# sch-arduino-uno-r3-v1.net
KiCad netlist of a schematic drawn in Altium Designer
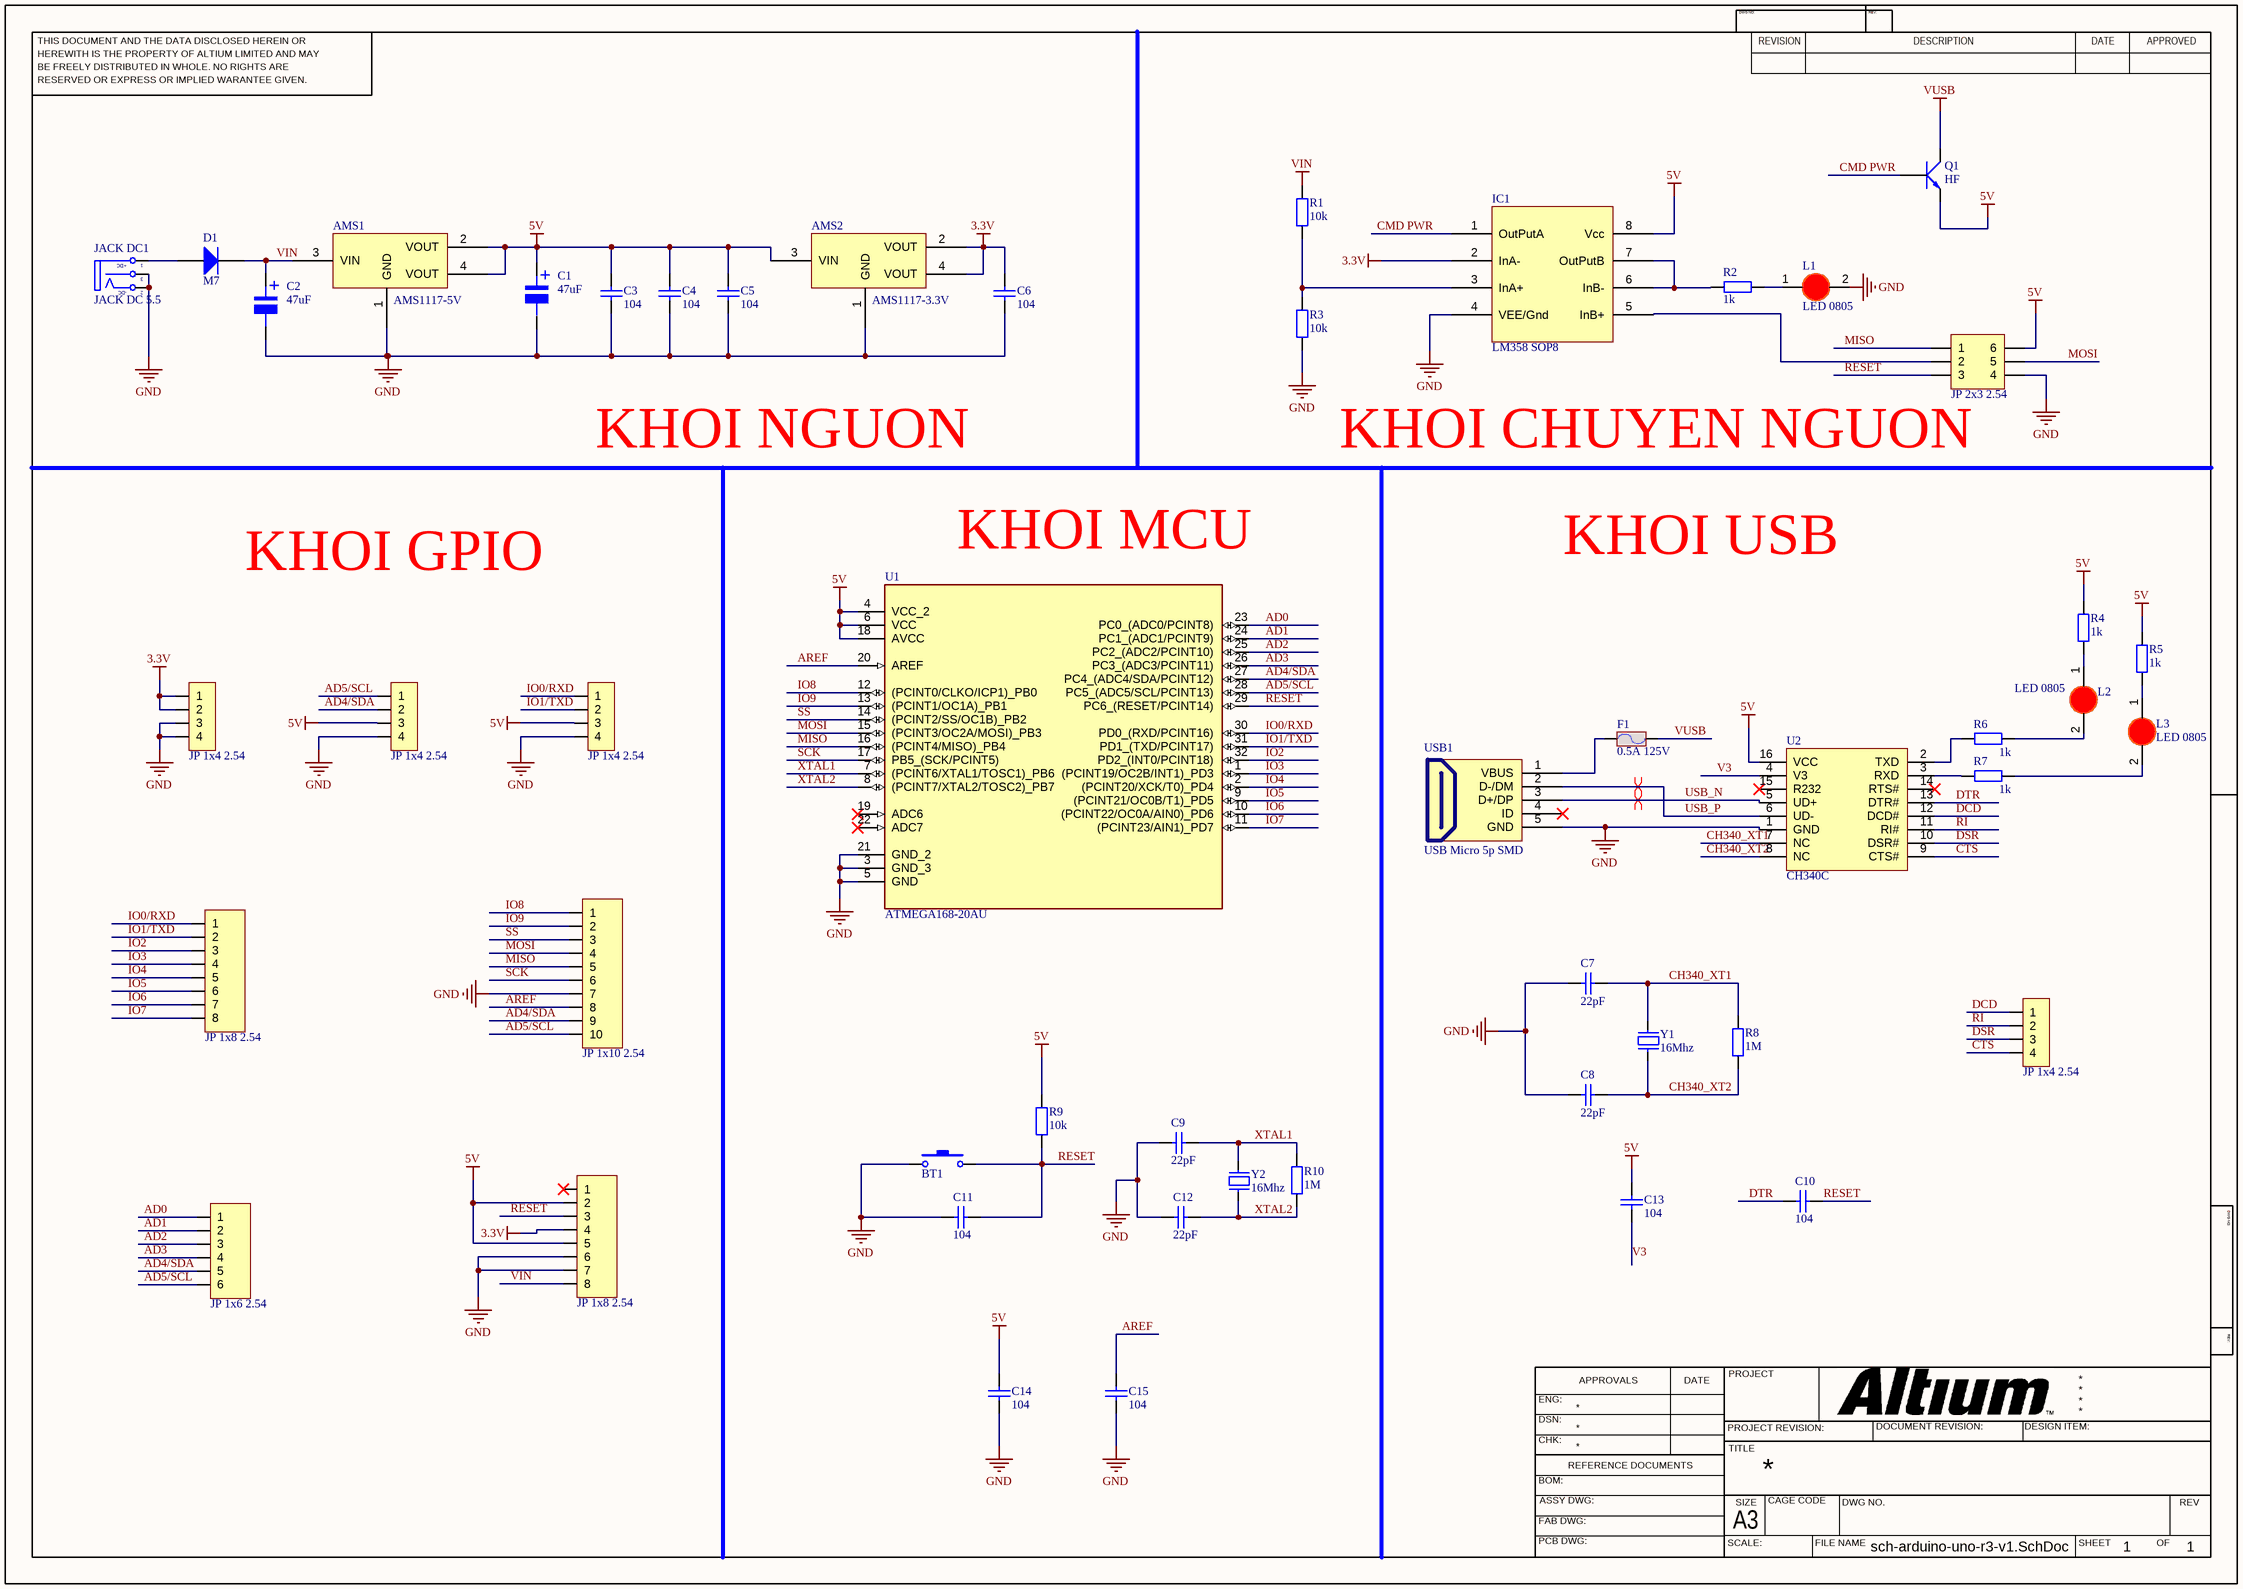
[diagram p0: sch-arduino-uno-r3-v1.SchDoc]

(export (version "E")
  (design (tool "Eeschema 10.0.6"))
  (components
    (comp (ref "AMS1")
      (value "AMS1117-5V")
      (footprint "SOT223")
      (description "Dán")
      (libsource (lib "Prj_ArduinoUno_Khanh") (part "AMS1117 SMD"))
    )
    (comp (ref "AMS2")
      (value "AMS1117-3.3V")
      (footprint "SOT223")
      (description "Dán")
      (libsource (lib "Prj_ArduinoUno_Khanh") (part "AMS1117 SMD_1"))
    )
    (comp (ref "BT1")
      (value "Nut Nhan 2 Chan SMD 3x6x2.5")
      (footprint "Nut Nhan 2 Chan SMD 3x6x2.5")
      (libsource (lib "Prj_ArduinoUno_Khanh") (part "Nut Nhan 2 Chan SMD 3x6x2.5"))
    )
    (comp (ref "C1")
      (value "47uF")
      (footprint "tu nhom 6.3 (d)")
      (description "Dán")
      (libsource (lib "Prj_ArduinoUno_Khanh") (part "Tu Nhom 47uF 50V"))
    )
    (comp (ref "C2")
      (value "47uF")
      (footprint "tu nhom 6.3 (d)")
      (description "Dán")
      (libsource (lib "Prj_ArduinoUno_Khanh") (part "Tu Nhom 47uF 50V"))
    )
    (comp (ref "C3")
      (value "104")
      (footprint "tu 0805")
      (description "Dán")
      (libsource (lib "Prj_ArduinoUno_Khanh") (part "Tu 0805 104 50V 10%"))
    )
    (comp (ref "C4")
      (value "104")
      (footprint "tu 0805")
      (description "Dán")
      (libsource (lib "Prj_ArduinoUno_Khanh") (part "Tu 0805 104 50V 10%"))
    )
    (comp (ref "C5")
      (value "104")
      (footprint "tu 0805")
      (description "Dán")
      (libsource (lib "Prj_ArduinoUno_Khanh") (part "Tu 0805 104 50V 10%"))
    )
    (comp (ref "C6")
      (value "104")
      (footprint "tu 0805")
      (description "Dán")
      (libsource (lib "Prj_ArduinoUno_Khanh") (part "Tu 0805 104 50V 10%"))
    )
    (comp (ref "C7")
      (value "22pF")
      (footprint "tu 0805")
      (description "Dán")
      (libsource (lib "Prj_ArduinoUno_Khanh") (part "Tu 0805 22pF 50V 10%"))
    )
    (comp (ref "C8")
      (value "22pF")
      (footprint "tu 0805")
      (description "Dán")
      (libsource (lib "Prj_ArduinoUno_Khanh") (part "Tu 0805 22pF 50V 10%"))
    )
    (comp (ref "C9")
      (value "22pF")
      (footprint "tu 0805")
      (description "Dán")
      (libsource (lib "Prj_ArduinoUno_Khanh") (part "Tu 0805 22pF 50V 10%"))
    )
    (comp (ref "C10")
      (value "104")
      (footprint "tu 0805")
      (description "Dán")
      (libsource (lib "Prj_ArduinoUno_Khanh") (part "Tu 0805 104 50V 10%"))
    )
    (comp (ref "C11")
      (value "104")
      (footprint "tu 0805")
      (description "Dán")
      (libsource (lib "Prj_ArduinoUno_Khanh") (part "Tu 0805 104 50V 10%"))
    )
    (comp (ref "C12")
      (value "22pF")
      (footprint "tu 0805")
      (description "Dán")
      (libsource (lib "Prj_ArduinoUno_Khanh") (part "Tu 0805 22pF 50V 10%"))
    )
    (comp (ref "C13")
      (value "104")
      (footprint "tu 0805")
      (description "Dán")
      (libsource (lib "Prj_ArduinoUno_Khanh") (part "Tu 0805 104 50V 10%"))
    )
    (comp (ref "C14")
      (value "104")
      (footprint "tu 0805")
      (description "Dán")
      (libsource (lib "Prj_ArduinoUno_Khanh") (part "Tu 0805 104 50V 10%"))
    )
    (comp (ref "C15")
      (value "104")
      (footprint "tu 0805")
      (description "Dán")
      (libsource (lib "Prj_ArduinoUno_Khanh") (part "Tu 0805 104 50V 10%"))
    )
    (comp (ref "D1")
      (value "M7")
      (footprint "DIODE SMA")
      (description "Dán")
      (libsource (lib "Prj_ArduinoUno_Khanh") (part "Diode M7 ( 4007 )"))
    )
    (comp (ref "F1")
      (value "0.5A 125V")
      (footprint "Cau Chi SMD1808")
      (description "Cau chi 0.5A 125V SMD1808")
      (libsource (lib "Prj_ArduinoUno_Khanh") (part "Cau chi 0.5A 125V SMD1808"))
    )
    (comp (ref "IC1")
      (value "LM358 SOP8")
      (footprint "SOP 8")
      (description "Dán")
      (libsource (lib "Prj_ArduinoUno_Khanh") (part "LM358 SOP8"))
    )
    (comp (ref "JACK DC1")
      (value "JACK DC 5.5")
      (footprint "JACK DC 5.5")
      (libsource (lib "Prj_ArduinoUno_Khanh") (part "JACK DC 5.5"))
    )
    (comp (ref "JP1")
      (value "JP 2x3 2.54")
      (footprint "JP 2x3 DT")
      (description "Cắm")
      (libsource (lib "Prj_ArduinoUno_Khanh") (part "JP 2x3 2.54 Duc Thang"))
    )
    (comp (ref "JP2")
      (value "JP 1x4 2.54")
      (footprint "JP 1x4 DT")
      (description "Cắm")
      (libsource (lib "Prj_ArduinoUno_Khanh") (part "JP 1x4 2.54 Duc Thang"))
    )
    (comp (ref "JP3")
      (value "JP 1x4 2.54")
      (footprint "JP 1x4 DT")
      (description "Cắm")
      (libsource (lib "Prj_ArduinoUno_Khanh") (part "JP 1x4 2.54 Duc Thang"))
    )
    (comp (ref "JP4")
      (value "JP 1x4 2.54")
      (footprint "JP 1x4 DT")
      (description "Cắm")
      (libsource (lib "Prj_ArduinoUno_Khanh") (part "JP 1x4 2.54 Duc Thang"))
    )
    (comp (ref "JP5")
      (value "JP 1x10 2.54")
      (footprint "JP 1x10 CT")
      (description "Cắm")
      (libsource (lib "Prj_ArduinoUno_Khanh") (part "JP 1x10 2.54 Cai Thang"))
    )
    (comp (ref "JP6")
      (value "JP 1x8 2.54")
      (footprint "JP 1x8 CT")
      (description "Cắm")
      (libsource (lib "Prj_ArduinoUno_Khanh") (part "JP 1x8 2.54 Cai Thang"))
    )
    (comp (ref "JP7")
      (value "JP 1x4 2.54")
      (footprint "JP 1x4 DT")
      (description "Cắm")
      (libsource (lib "Prj_ArduinoUno_Khanh") (part "JP 1x4 2.54 Duc Thang"))
    )
    (comp (ref "JP8")
      (value "JP 1x8 2.54")
      (footprint "JP 1x8 CT")
      (description "Cắm")
      (libsource (lib "Prj_ArduinoUno_Khanh") (part "JP 1x8 2.54 Cai Thang"))
    )
    (comp (ref "JP9")
      (value "JP 1x6 2.54")
      (footprint "JP 1x6 CT")
      (description "Cắm")
      (libsource (lib "Prj_ArduinoUno_Khanh") (part "JP 1x6 2.54 Cai Thang"))
    )
    (comp (ref "L1")
      (value "LED 0805")
      (footprint "LED-0805-Red")
      (description "Dán")
      (libsource (lib "Prj_ArduinoUno_Khanh") (part "LED 0805 Do"))
    )
    (comp (ref "L2")
      (value "LED 0805")
      (footprint "LED-0805-Red")
      (description "Dán")
      (libsource (lib "Prj_ArduinoUno_Khanh") (part "LED 0805 Do"))
    )
    (comp (ref "L3")
      (value "LED 0805")
      (footprint "LED-0805-Red")
      (description "Dán")
      (libsource (lib "Prj_ArduinoUno_Khanh") (part "LED 0805 Do"))
    )
    (comp (ref "Q1")
      (value "HF")
      (footprint "SOT23")
      (description "NPN transistor")
      (libsource (lib "Prj_ArduinoUno_Khanh") (part "C1815 HF SMD"))
    )
    (comp (ref "R1")
      (value "10k")
      (footprint "tro smd 0805")
      (description "Dán")
      (libsource (lib "Prj_ArduinoUno_Khanh") (part "Tro 0805 5% 10k"))
    )
    (comp (ref "R2")
      (value "1k")
      (footprint "tro smd 0805")
      (description "Dán")
      (libsource (lib "Prj_ArduinoUno_Khanh") (part "Tro 0805 1% 1k"))
    )
    (comp (ref "R3")
      (value "10k")
      (footprint "tro smd 0805")
      (description "Dán")
      (libsource (lib "Prj_ArduinoUno_Khanh") (part "Tro 0805 5% 10k"))
    )
    (comp (ref "R4")
      (value "1k")
      (footprint "tro smd 0805")
      (description "Dán")
      (libsource (lib "Prj_ArduinoUno_Khanh") (part "Tro 0805 1% 1k"))
    )
    (comp (ref "R5")
      (value "1k")
      (footprint "tro smd 0805")
      (description "Dán")
      (libsource (lib "Prj_ArduinoUno_Khanh") (part "Tro 0805 1% 1k"))
    )
    (comp (ref "R6")
      (value "1k")
      (footprint "tro smd 0805")
      (description "Dán")
      (libsource (lib "Prj_ArduinoUno_Khanh") (part "Tro 0805 1% 1k"))
    )
    (comp (ref "R7")
      (value "1k")
      (footprint "tro smd 0805")
      (description "Dán")
      (libsource (lib "Prj_ArduinoUno_Khanh") (part "Tro 0805 1% 1k"))
    )
    (comp (ref "R8")
      (value "1M")
      (footprint "tro smd 0805")
      (description "Dán")
      (libsource (lib "Prj_ArduinoUno_Khanh") (part "Tro 0805 5% 1M"))
    )
    (comp (ref "R9")
      (value "10k")
      (footprint "tro smd 0805")
      (description "Dán")
      (libsource (lib "Prj_ArduinoUno_Khanh") (part "Tro 0805 5% 10k"))
    )
    (comp (ref "R10")
      (value "1M")
      (footprint "tro smd 0805")
      (description "Dán")
      (libsource (lib "Prj_ArduinoUno_Khanh") (part "Tro 0805 5% 1M"))
    )
    (comp (ref "U1")
      (value "ATMEGA168-20AU")
      (footprint "ATMEGA168")
      (description "AVR AVRÂ® ATmega Microcontroller IC 8-Bit 20MHz 16KB _8K x 16_ FLASH 32-TQFP _7x7_")
      (fields (field (name "MF") "Microchip"))
      (libsource (lib "Prj_ArduinoUno_Khanh") (part "ATMEGA168-20AU"))
    )
    (comp (ref "U2")
      (value "CH340C")
      (footprint "SOIC16_50_284_25X90_SMT")
      (description "USB Bridge, USB to UART USB 2.0 UART Interface")
      (fields (field (name "MANUFACTURER") "Olimex"))
      (libsource (lib "Prj_ArduinoUno_Khanh") (part "IC_CH340C"))
    )
    (comp (ref "USB1")
      (value "USB Micro 5p SMD")
      (footprint "USB Micro 5p SMD")
      (description "USB Type B")
      (libsource (lib "Prj_ArduinoUno_Khanh") (part "USB Micro 5p SMD"))
    )
    (comp (ref "Y1")
      (value "16Mhz")
      (footprint "Thach Anh 2 chan SMD")
      (description "Crystal For all Crystal 2pin.")
      (libsource (lib "Prj_ArduinoUno_Khanh") (part "Thach Anh 2 chan SMD"))
    )
    (comp (ref "Y2")
      (value "16Mhz")
      (footprint "Thach Anh 2 chan SMD")
      (description "Crystal For all Crystal 2pin.")
      (libsource (lib "Prj_ArduinoUno_Khanh") (part "Thach Anh 2 chan SMD"))
    )
  )
  (nets
    (net (code "1") (name "/AD0") (class "Default")
      (node (ref "JP9") (pin "1") (pinfunction "1_1") (pintype "passive"))
      (node (ref "U1") (pin "23") (pinfunction "PC0_(ADC0/PCINT8)_23") (pintype "bidirectional"))
    )
    (net (code "2") (name "/AD1") (class "Default")
      (node (ref "JP9") (pin "2") (pinfunction "2_2") (pintype "passive"))
      (node (ref "U1") (pin "24") (pinfunction "PC1_(ADC1/PCINT9)_24") (pintype "bidirectional"))
    )
    (net (code "3") (name "/AD2") (class "Default")
      (node (ref "JP9") (pin "3") (pinfunction "3_3") (pintype "passive"))
      (node (ref "U1") (pin "25") (pinfunction "PC2_(ADC2/PCINT10)_25") (pintype "bidirectional"))
    )
    (net (code "4") (name "/AD3") (class "Default")
      (node (ref "JP9") (pin "4") (pinfunction "4_4") (pintype "passive"))
      (node (ref "U1") (pin "26") (pinfunction "PC3_(ADC3/PCINT11)_26") (pintype "bidirectional"))
    )
    (net (code "5") (name "/AD4{slash}SDA") (class "Default")
      (node (ref "JP3") (pin "2") (pinfunction "2_2") (pintype "passive"))
      (node (ref "JP5") (pin "9") (pinfunction "9_9") (pintype "passive"))
      (node (ref "JP9") (pin "5") (pinfunction "5_5") (pintype "passive"))
      (node (ref "U1") (pin "27") (pinfunction "PC4_(ADC4/SDA/PCINT12)_27") (pintype "bidirectional"))
    )
    (net (code "6") (name "/AD5{slash}SCL") (class "Default")
      (node (ref "JP3") (pin "1") (pinfunction "1_1") (pintype "passive"))
      (node (ref "JP5") (pin "10") (pinfunction "10_10") (pintype "passive"))
      (node (ref "JP9") (pin "6") (pinfunction "6_6") (pintype "passive"))
      (node (ref "U1") (pin "28") (pinfunction "PC5_(ADC5/SCL/PCINT13)_28") (pintype "bidirectional"))
    )
    (net (code "7") (name "/AREF") (class "Default")
      (node (ref "C15") (pin "1") (pinfunction "1_1") (pintype "passive"))
      (node (ref "JP5") (pin "8") (pinfunction "8_8") (pintype "passive"))
      (node (ref "U1") (pin "20") (pinfunction "AREF_20") (pintype "input"))
    )
    (net (code "8") (name "/CH340_XT1") (class "Default")
      (node (ref "C7") (pin "1") (pinfunction "1_1") (pintype "passive"))
      (node (ref "R8") (pin "2") (pinfunction "2_2") (pintype "passive"))
      (node (ref "U2") (pin "7") (pinfunction "NC_7") (pintype "passive"))
      (node (ref "Y1") (pin "2") (pinfunction "2_2") (pintype "passive"))
    )
    (net (code "9") (name "/CH340_XT2") (class "Default")
      (node (ref "C8") (pin "1") (pinfunction "1_1") (pintype "passive"))
      (node (ref "R8") (pin "1") (pinfunction "1_1") (pintype "passive"))
      (node (ref "U2") (pin "8") (pinfunction "NC_8") (pintype "passive"))
      (node (ref "Y1") (pin "1") (pinfunction "1_1") (pintype "passive"))
    )
    (net (code "10") (name "/CMD PWR") (class "Default")
      (node (ref "IC1") (pin "1") (pinfunction "OutPutA_1") (pintype "passive"))
      (node (ref "Q1") (pin "1") (pinfunction "B_1") (pintype "passive"))
    )
    (net (code "11") (name "/CTS") (class "Default")
      (node (ref "JP7") (pin "4") (pinfunction "4_4") (pintype "passive"))
      (node (ref "U2") (pin "9") (pinfunction "CTS#_9") (pintype "passive"))
    )
    (net (code "12") (name "/DCD") (class "Default")
      (node (ref "JP7") (pin "1") (pinfunction "1_1") (pintype "passive"))
      (node (ref "U2") (pin "12") (pinfunction "DCD#_12") (pintype "passive"))
    )
    (net (code "13") (name "/DSR") (class "Default")
      (node (ref "JP7") (pin "3") (pinfunction "3_3") (pintype "passive"))
      (node (ref "U2") (pin "10") (pinfunction "DSR#_10") (pintype "passive"))
    )
    (net (code "14") (name "/DTR") (class "Default")
      (node (ref "C10") (pin "1") (pinfunction "1_1") (pintype "passive"))
      (node (ref "U2") (pin "13") (pinfunction "DTR#_13") (pintype "passive"))
    )
    (net (code "15") (name "/IO0{slash}RXD") (class "Default")
      (node (ref "JP4") (pin "1") (pinfunction "1_1") (pintype "passive"))
      (node (ref "JP6") (pin "1") (pinfunction "1_1") (pintype "passive"))
      (node (ref "U1") (pin "30") (pinfunction "PD0_(RXD/PCINT16)_30") (pintype "bidirectional"))
    )
    (net (code "16") (name "/IO1{slash}TXD") (class "Default")
      (node (ref "JP4") (pin "2") (pinfunction "2_2") (pintype "passive"))
      (node (ref "JP6") (pin "2") (pinfunction "2_2") (pintype "passive"))
      (node (ref "U1") (pin "31") (pinfunction "PD1_(TXD/PCINT17)_31") (pintype "bidirectional"))
    )
    (net (code "17") (name "/IO2") (class "Default")
      (node (ref "JP6") (pin "3") (pinfunction "3_3") (pintype "passive"))
      (node (ref "U1") (pin "32") (pinfunction "PD2_(INT0/PCINT18)_32") (pintype "bidirectional"))
    )
    (net (code "18") (name "/IO3") (class "Default")
      (node (ref "JP6") (pin "4") (pinfunction "4_4") (pintype "passive"))
      (node (ref "U1") (pin "1") (pinfunction "(PCINT19/OC2B/INT1)_PD3_1") (pintype "bidirectional"))
    )
    (net (code "19") (name "/IO4") (class "Default")
      (node (ref "JP6") (pin "5") (pinfunction "5_5") (pintype "passive"))
      (node (ref "U1") (pin "2") (pinfunction "(PCINT20/XCK/T0)_PD4_2") (pintype "bidirectional"))
    )
    (net (code "20") (name "/IO5") (class "Default")
      (node (ref "JP6") (pin "6") (pinfunction "6_6") (pintype "passive"))
      (node (ref "U1") (pin "9") (pinfunction "(PCINT21/OC0B/T1)_PD5_9") (pintype "bidirectional"))
    )
    (net (code "21") (name "/IO6") (class "Default")
      (node (ref "JP6") (pin "7") (pinfunction "7_7") (pintype "passive"))
      (node (ref "U1") (pin "10") (pinfunction "(PCINT22/OC0A/AIN0)_PD6_10") (pintype "bidirectional"))
    )
    (net (code "22") (name "/IO7") (class "Default")
      (node (ref "JP6") (pin "8") (pinfunction "8_8") (pintype "passive"))
      (node (ref "U1") (pin "11") (pinfunction "(PCINT23/AIN1)_PD7_11") (pintype "bidirectional"))
    )
    (net (code "23") (name "/IO8") (class "Default")
      (node (ref "JP5") (pin "1") (pinfunction "1_1") (pintype "passive"))
      (node (ref "U1") (pin "12") (pinfunction "(PCINT0/CLKO/ICP1)_PB0_12") (pintype "bidirectional"))
    )
    (net (code "24") (name "/IO9") (class "Default")
      (node (ref "JP5") (pin "2") (pinfunction "2_2") (pintype "passive"))
      (node (ref "U1") (pin "13") (pinfunction "(PCINT1/OC1A)_PB1_13") (pintype "bidirectional"))
    )
    (net (code "25") (name "/MISO") (class "Default")
      (node (ref "JP1") (pin "1") (pinfunction "1_1") (pintype "passive"))
      (node (ref "JP5") (pin "5") (pinfunction "5_5") (pintype "passive"))
      (node (ref "U1") (pin "16") (pinfunction "(PCINT4/MISO)_PB4_16") (pintype "bidirectional"))
    )
    (net (code "26") (name "/MOSI") (class "Default")
      (node (ref "JP1") (pin "5") (pinfunction "5_5") (pintype "passive"))
      (node (ref "JP5") (pin "4") (pinfunction "4_4") (pintype "passive"))
      (node (ref "U1") (pin "15") (pinfunction "(PCINT3/OC2A/MOSI)_PB3_15") (pintype "bidirectional"))
    )
    (net (code "27") (name "/RESET") (class "Default")
      (node (ref "BT1") (pin "2") (pinfunction "2_2") (pintype "passive"))
      (node (ref "C10") (pin "2") (pinfunction "2_2") (pintype "passive"))
      (node (ref "C11") (pin "1") (pinfunction "1_1") (pintype "passive"))
      (node (ref "JP1") (pin "3") (pinfunction "3_3") (pintype "passive"))
      (node (ref "JP8") (pin "3") (pinfunction "3_3") (pintype "passive"))
      (node (ref "R9") (pin "1") (pinfunction "1_1") (pintype "passive"))
      (node (ref "U1") (pin "29") (pinfunction "PC6_(RESET/PCINT14)_29") (pintype "bidirectional"))
    )
    (net (code "28") (name "/RI") (class "Default")
      (node (ref "JP7") (pin "2") (pinfunction "2_2") (pintype "passive"))
      (node (ref "U2") (pin "11") (pinfunction "RI#_11") (pintype "passive"))
    )
    (net (code "29") (name "/SCK") (class "Default")
      (node (ref "JP5") (pin "6") (pinfunction "6_6") (pintype "passive"))
      (node (ref "U1") (pin "17") (pinfunction "PB5_(SCK/PCINT5)_17") (pintype "bidirectional"))
    )
    (net (code "30") (name "/SS") (class "Default")
      (node (ref "JP5") (pin "3") (pinfunction "3_3") (pintype "passive"))
      (node (ref "U1") (pin "14") (pinfunction "(PCINT2/SS/OC1B)_PB2_14") (pintype "bidirectional"))
    )
    (net (code "31") (name "/USB_N") (class "Default")
      (node (ref "U2") (pin "5") (pinfunction "UD+_5") (pintype "passive"))
      (node (ref "USB1") (pin "3") (pinfunction "D+/DP_3") (pintype "passive"))
    )
    (net (code "32") (name "/USB_P") (class "Default")
      (node (ref "U2") (pin "6") (pinfunction "UD-_6") (pintype "passive"))
      (node (ref "USB1") (pin "2") (pinfunction "D-/DM_2") (pintype "passive"))
    )
    (net (code "33") (name "/V3") (class "Default")
      (node (ref "C13") (pin "2") (pinfunction "2_2") (pintype "passive"))
      (node (ref "U2") (pin "4") (pinfunction "V3_4") (pintype "passive"))
    )
    (net (code "34") (name "/XTAL1") (class "Default")
      (node (ref "C9") (pin "1") (pinfunction "1_1") (pintype "passive"))
      (node (ref "R10") (pin "2") (pinfunction "2_2") (pintype "passive"))
      (node (ref "U1") (pin "7") (pinfunction "(PCINT6/XTAL1/TOSC1)_PB6_7") (pintype "bidirectional"))
      (node (ref "Y2") (pin "2") (pinfunction "2_2") (pintype "passive"))
    )
    (net (code "35") (name "/XTAL2") (class "Default")
      (node (ref "C12") (pin "1") (pinfunction "1_1") (pintype "passive"))
      (node (ref "R10") (pin "1") (pinfunction "1_1") (pintype "passive"))
      (node (ref "U1") (pin "8") (pinfunction "(PCINT7/XTAL2/TOSC2)_PB7_8") (pintype "bidirectional"))
      (node (ref "Y2") (pin "1") (pinfunction "1_1") (pintype "passive"))
    )
    (net (code "36") (name "3.3V") (class "Default")
      (node (ref "AMS2") (pin "2") (pinfunction "VOUT_2") (pintype "passive"))
      (node (ref "AMS2") (pin "4") (pinfunction "VOUT_4") (pintype "passive"))
      (node (ref "C6") (pin "1") (pinfunction "1_1") (pintype "passive"))
      (node (ref "IC1") (pin "2") (pinfunction "InA-_2") (pintype "passive"))
      (node (ref "JP2") (pin "1") (pinfunction "1_1") (pintype "passive"))
      (node (ref "JP2") (pin "2") (pinfunction "2_2") (pintype "passive"))
      (node (ref "JP8") (pin "4") (pinfunction "4_4") (pintype "passive"))
    )
    (net (code "37") (name "5V") (class "Default")
      (node (ref "AMS1") (pin "2") (pinfunction "VOUT_2") (pintype "passive"))
      (node (ref "AMS1") (pin "4") (pinfunction "VOUT_4") (pintype "passive"))
      (node (ref "AMS2") (pin "3") (pinfunction "VIN_3") (pintype "passive"))
      (node (ref "C1") (pin "1") (pinfunction "1_1") (pintype "passive"))
      (node (ref "C13") (pin "1") (pinfunction "1_1") (pintype "passive"))
      (node (ref "C14") (pin "1") (pinfunction "1_1") (pintype "passive"))
      (node (ref "C3") (pin "1") (pinfunction "1_1") (pintype "passive"))
      (node (ref "C4") (pin "1") (pinfunction "1_1") (pintype "passive"))
      (node (ref "C5") (pin "1") (pinfunction "1_1") (pintype "passive"))
      (node (ref "IC1") (pin "8") (pinfunction "Vcc_8") (pintype "passive"))
      (node (ref "JP1") (pin "6") (pinfunction "6_6") (pintype "passive"))
      (node (ref "JP3") (pin "3") (pinfunction "3_3") (pintype "passive"))
      (node (ref "JP4") (pin "3") (pinfunction "3_3") (pintype "passive"))
      (node (ref "JP8") (pin "2") (pinfunction "2_2") (pintype "passive"))
      (node (ref "JP8") (pin "5") (pinfunction "5_5") (pintype "passive"))
      (node (ref "Q1") (pin "2") (pinfunction "E_2") (pintype "passive"))
      (node (ref "R4") (pin "2") (pinfunction "2_2") (pintype "passive"))
      (node (ref "R5") (pin "2") (pinfunction "2_2") (pintype "passive"))
      (node (ref "R9") (pin "2") (pinfunction "2_2") (pintype "passive"))
      (node (ref "U1") (pin "18") (pinfunction "AVCC_18") (pintype "power_in"))
      (node (ref "U1") (pin "4") (pinfunction "VCC_2_4") (pintype "power_in"))
      (node (ref "U1") (pin "6") (pinfunction "VCC_6") (pintype "power_in"))
      (node (ref "U2") (pin "16") (pinfunction "VCC_16") (pintype "passive"))
    )
    (net (code "38") (name "GND") (class "Default")
      (node (ref "AMS1") (pin "1") (pinfunction "GND_1") (pintype "passive"))
      (node (ref "AMS2") (pin "1") (pinfunction "GND_1") (pintype "passive"))
      (node (ref "BT1") (pin "1") (pinfunction "1_1") (pintype "passive"))
      (node (ref "C1") (pin "2") (pinfunction "2_2") (pintype "passive"))
      (node (ref "C11") (pin "2") (pinfunction "2_2") (pintype "passive"))
      (node (ref "C12") (pin "2") (pinfunction "2_2") (pintype "passive"))
      (node (ref "C14") (pin "2") (pinfunction "2_2") (pintype "passive"))
      (node (ref "C15") (pin "2") (pinfunction "2_2") (pintype "passive"))
      (node (ref "C2") (pin "2") (pinfunction "2_2") (pintype "passive"))
      (node (ref "C3") (pin "2") (pinfunction "2_2") (pintype "passive"))
      (node (ref "C4") (pin "2") (pinfunction "2_2") (pintype "passive"))
      (node (ref "C5") (pin "2") (pinfunction "2_2") (pintype "passive"))
      (node (ref "C6") (pin "2") (pinfunction "2_2") (pintype "passive"))
      (node (ref "C7") (pin "2") (pinfunction "2_2") (pintype "passive"))
      (node (ref "C8") (pin "2") (pinfunction "2_2") (pintype "passive"))
      (node (ref "C9") (pin "2") (pinfunction "2_2") (pintype "passive"))
      (node (ref "IC1") (pin "4") (pinfunction "VEE/Gnd_4") (pintype "passive"))
      (node (ref "JACK DC1") (pin "2") (pinfunction "TN_2") (pintype "passive"))
      (node (ref "JACK DC1") (pin "3") (pinfunction "S_3") (pintype "power_in"))
      (node (ref "JP1") (pin "4") (pinfunction "4_4") (pintype "passive"))
      (node (ref "JP2") (pin "3") (pinfunction "3_3") (pintype "passive"))
      (node (ref "JP2") (pin "4") (pinfunction "4_4") (pintype "passive"))
      (node (ref "JP3") (pin "4") (pinfunction "4_4") (pintype "passive"))
      (node (ref "JP4") (pin "4") (pinfunction "4_4") (pintype "passive"))
      (node (ref "JP5") (pin "7") (pinfunction "7_7") (pintype "passive"))
      (node (ref "JP8") (pin "6") (pinfunction "6_6") (pintype "passive"))
      (node (ref "JP8") (pin "7") (pinfunction "7_7") (pintype "passive"))
      (node (ref "L1") (pin "2") (pinfunction "K_2") (pintype "passive"))
      (node (ref "R3") (pin "1") (pinfunction "1_1") (pintype "passive"))
      (node (ref "U1") (pin "21") (pinfunction "GND_2_21") (pintype "passive"))
      (node (ref "U1") (pin "3") (pinfunction "GND_3_3") (pintype "passive"))
      (node (ref "U1") (pin "5") (pinfunction "GND_5") (pintype "passive"))
      (node (ref "U2") (pin "1") (pinfunction "GND_1") (pintype "passive"))
      (node (ref "USB1") (pin "5") (pinfunction "GND_5") (pintype "passive"))
    )
    (net (code "39") (name "Net-(D1-A)") (class "Default")
      (node (ref "D1") (pin "1") (pinfunction "A_1") (pintype "passive"))
      (node (ref "JACK DC1") (pin "1") (pinfunction "T_1") (pintype "passive"))
    )
    (net (code "40") (name "Net-(IC1-InA+)") (class "Default")
      (node (ref "IC1") (pin "3") (pinfunction "InA+_3") (pintype "passive"))
      (node (ref "R1") (pin "1") (pinfunction "1_1") (pintype "passive"))
      (node (ref "R3") (pin "2") (pinfunction "2_2") (pintype "passive"))
    )
    (net (code "41") (name "Net-(IC1-InB+)") (class "Default")
      (node (ref "IC1") (pin "5") (pinfunction "InB+_5") (pintype "passive"))
      (node (ref "JP1") (pin "2") (pinfunction "2_2") (pintype "passive"))
    )
    (net (code "42") (name "Net-(IC1-InB-)") (class "Default")
      (node (ref "IC1") (pin "6") (pinfunction "InB-_6") (pintype "passive"))
      (node (ref "IC1") (pin "7") (pinfunction "OutPutB_7") (pintype "passive"))
      (node (ref "R2") (pin "1") (pinfunction "1_1") (pintype "passive"))
    )
    (net (code "43") (name "Net-(L1-A)") (class "Default")
      (node (ref "L1") (pin "1") (pinfunction "A_1") (pintype "passive"))
      (node (ref "R2") (pin "2") (pinfunction "2_2") (pintype "passive"))
    )
    (net (code "44") (name "Net-(L2-A)") (class "Default")
      (node (ref "L2") (pin "1") (pinfunction "A_1") (pintype "passive"))
      (node (ref "R4") (pin "1") (pinfunction "1_1") (pintype "passive"))
    )
    (net (code "45") (name "Net-(L2-K)") (class "Default")
      (node (ref "L2") (pin "2") (pinfunction "K_2") (pintype "passive"))
      (node (ref "R6") (pin "2") (pinfunction "2_2") (pintype "passive"))
    )
    (net (code "46") (name "Net-(L3-A)") (class "Default")
      (node (ref "L3") (pin "1") (pinfunction "A_1") (pintype "passive"))
      (node (ref "R5") (pin "1") (pinfunction "1_1") (pintype "passive"))
    )
    (net (code "47") (name "Net-(L3-K)") (class "Default")
      (node (ref "L3") (pin "2") (pinfunction "K_2") (pintype "passive"))
      (node (ref "R7") (pin "2") (pinfunction "2_2") (pintype "passive"))
    )
    (net (code "48") (name "Net-(U2-RXD)") (class "Default")
      (node (ref "R7") (pin "1") (pinfunction "1_1") (pintype "passive"))
      (node (ref "U2") (pin "3") (pinfunction "RXD_3") (pintype "passive"))
    )
    (net (code "49") (name "Net-(U2-TXD)") (class "Default")
      (node (ref "R6") (pin "1") (pinfunction "1_1") (pintype "passive"))
      (node (ref "U2") (pin "2") (pinfunction "TXD_2") (pintype "passive"))
    )
    (net (code "50") (name "Net-(USB1-VBUS)") (class "Default")
      (node (ref "F1") (pin "1") (pinfunction "1_1") (pintype "passive"))
      (node (ref "USB1") (pin "1") (pinfunction "VBUS_1") (pintype "passive"))
    )
    (net (code "51") (name "VIN") (class "Default")
      (node (ref "AMS1") (pin "3") (pinfunction "VIN_3") (pintype "passive"))
      (node (ref "C2") (pin "1") (pinfunction "1_1") (pintype "passive"))
      (node (ref "D1") (pin "2") (pinfunction "K_2") (pintype "passive"))
      (node (ref "JP8") (pin "8") (pinfunction "8_8") (pintype "passive"))
      (node (ref "R1") (pin "2") (pinfunction "2_2") (pintype "passive"))
    )
    (net (code "52") (name "VUSB") (class "Default")
      (node (ref "F1") (pin "2") (pinfunction "2_2") (pintype "passive"))
      (node (ref "Q1") (pin "3") (pinfunction "C_3") (pintype "passive"))
    )
    (net (code "53") (name "unconnected-(JP8-Pad1)") (class "Default")
      (node (ref "JP8") (pin "1") (pinfunction "1_1") (pintype "passive+no_connect"))
    )
    (net (code "54") (name "unconnected-(U1-ADC6-Pad19)") (class "Default")
      (node (ref "U1") (pin "19") (pinfunction "ADC6_19") (pintype "input+no_connect"))
    )
    (net (code "55") (name "unconnected-(U1-ADC7-Pad22)") (class "Default")
      (node (ref "U1") (pin "22") (pinfunction "ADC7_22") (pintype "input+no_connect"))
    )
    (net (code "56") (name "unconnected-(U2-R232-Pad15)") (class "Default")
      (node (ref "U2") (pin "15") (pinfunction "R232_15") (pintype "passive+no_connect"))
    )
    (net (code "57") (name "unconnected-(U2-RTS#-Pad14)") (class "Default")
      (node (ref "U2") (pin "14") (pinfunction "RTS#_14") (pintype "passive+no_connect"))
    )
    (net (code "58") (name "unconnected-(USB1-ID-Pad4)") (class "Default")
      (node (ref "USB1") (pin "4") (pinfunction "ID_4") (pintype "passive+no_connect"))
    )
  )
)
